# APA102_Shield.net
KiCad netlist of a schematic drawn in EAGLE
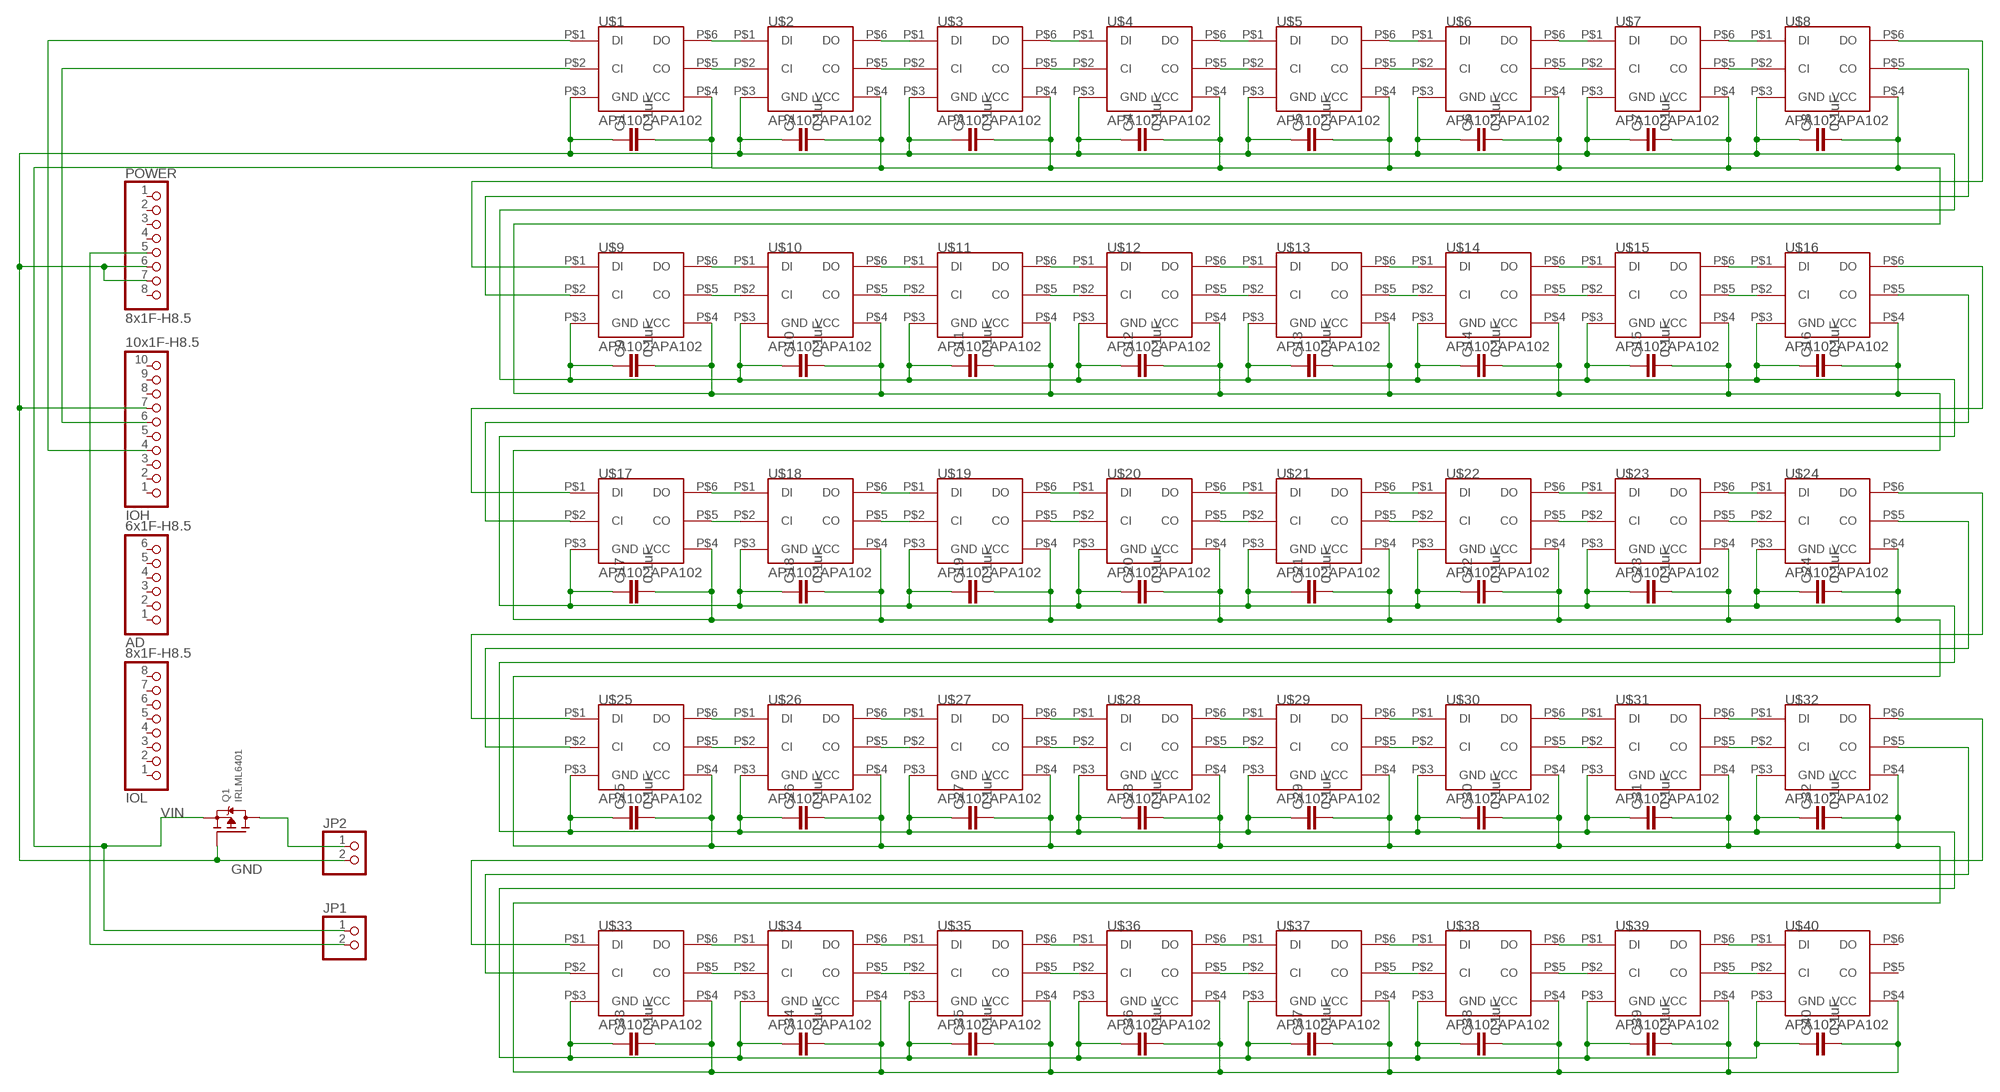
[diagram p0: schematic, sheet 1]

(export (version "E")
  (design (tool "Eeschema 10.0.6"))
  (components
    (comp (ref "AD")
      (value "6x1F-H8.5")
      (footprint "eagle-import:1X06")
      (libsource (lib "eagle-import") (part "PINHD-1X6"))
    )
    (comp (ref "C1")
      (value "0.1uF")
      (footprint "eagle-import:C1206")
      (libsource (lib "eagle-import") (part "C-EUC1206"))
    )
    (comp (ref "C2")
      (value "0.1uF")
      (footprint "eagle-import:C1206")
      (libsource (lib "eagle-import") (part "C-EUC1206"))
    )
    (comp (ref "C3")
      (value "0.1uF")
      (footprint "eagle-import:C1206")
      (libsource (lib "eagle-import") (part "C-EUC1206"))
    )
    (comp (ref "C4")
      (value "0.1uF")
      (footprint "eagle-import:C1206")
      (libsource (lib "eagle-import") (part "C-EUC1206"))
    )
    (comp (ref "C5")
      (value "0.1uF")
      (footprint "eagle-import:C1206")
      (libsource (lib "eagle-import") (part "C-EUC1206"))
    )
    (comp (ref "C6")
      (value "0.1uF")
      (footprint "eagle-import:C1206")
      (libsource (lib "eagle-import") (part "C-EUC1206"))
    )
    (comp (ref "C7")
      (value "0.1uF")
      (footprint "eagle-import:C1206")
      (libsource (lib "eagle-import") (part "C-EUC1206"))
    )
    (comp (ref "C8")
      (value "0.1uF")
      (footprint "eagle-import:C1206")
      (libsource (lib "eagle-import") (part "C-EUC1206"))
    )
    (comp (ref "C9")
      (value "0.1uF")
      (footprint "eagle-import:C1206")
      (libsource (lib "eagle-import") (part "C-EUC1206"))
    )
    (comp (ref "C10")
      (value "0.1uF")
      (footprint "eagle-import:C1206")
      (libsource (lib "eagle-import") (part "C-EUC1206"))
    )
    (comp (ref "C11")
      (value "0.1uF")
      (footprint "eagle-import:C1206")
      (libsource (lib "eagle-import") (part "C-EUC1206"))
    )
    (comp (ref "C12")
      (value "0.1uF")
      (footprint "eagle-import:C1206")
      (libsource (lib "eagle-import") (part "C-EUC1206"))
    )
    (comp (ref "C13")
      (value "0.1uF")
      (footprint "eagle-import:C1206")
      (libsource (lib "eagle-import") (part "C-EUC1206"))
    )
    (comp (ref "C14")
      (value "0.1uF")
      (footprint "eagle-import:C1206")
      (libsource (lib "eagle-import") (part "C-EUC1206"))
    )
    (comp (ref "C15")
      (value "0.1uF")
      (footprint "eagle-import:C1206")
      (libsource (lib "eagle-import") (part "C-EUC1206"))
    )
    (comp (ref "C16")
      (value "0.1uF")
      (footprint "eagle-import:C1206")
      (libsource (lib "eagle-import") (part "C-EUC1206"))
    )
    (comp (ref "C17")
      (value "0.1uF")
      (footprint "eagle-import:C1206")
      (libsource (lib "eagle-import") (part "C-EUC1206"))
    )
    (comp (ref "C18")
      (value "0.1uF")
      (footprint "eagle-import:C1206")
      (libsource (lib "eagle-import") (part "C-EUC1206"))
    )
    (comp (ref "C19")
      (value "0.1uF")
      (footprint "eagle-import:C1206")
      (libsource (lib "eagle-import") (part "C-EUC1206"))
    )
    (comp (ref "C20")
      (value "0.1uF")
      (footprint "eagle-import:C1206")
      (libsource (lib "eagle-import") (part "C-EUC1206"))
    )
    (comp (ref "C21")
      (value "0.1uF")
      (footprint "eagle-import:C1206")
      (libsource (lib "eagle-import") (part "C-EUC1206"))
    )
    (comp (ref "C22")
      (value "0.1uF")
      (footprint "eagle-import:C1206")
      (libsource (lib "eagle-import") (part "C-EUC1206"))
    )
    (comp (ref "C23")
      (value "0.1uF")
      (footprint "eagle-import:C1206")
      (libsource (lib "eagle-import") (part "C-EUC1206"))
    )
    (comp (ref "C24")
      (value "0.1uF")
      (footprint "eagle-import:C1206")
      (libsource (lib "eagle-import") (part "C-EUC1206"))
    )
    (comp (ref "C25")
      (value "0.1uF")
      (footprint "eagle-import:C1206")
      (libsource (lib "eagle-import") (part "C-EUC1206"))
    )
    (comp (ref "C26")
      (value "0.1uF")
      (footprint "eagle-import:C1206")
      (libsource (lib "eagle-import") (part "C-EUC1206"))
    )
    (comp (ref "C27")
      (value "0.1uF")
      (footprint "eagle-import:C1206")
      (libsource (lib "eagle-import") (part "C-EUC1206"))
    )
    (comp (ref "C28")
      (value "0.1uF")
      (footprint "eagle-import:C1206")
      (libsource (lib "eagle-import") (part "C-EUC1206"))
    )
    (comp (ref "C29")
      (value "0.1uF")
      (footprint "eagle-import:C1206")
      (libsource (lib "eagle-import") (part "C-EUC1206"))
    )
    (comp (ref "C30")
      (value "0.1uF")
      (footprint "eagle-import:C1206")
      (libsource (lib "eagle-import") (part "C-EUC1206"))
    )
    (comp (ref "C31")
      (value "0.1uF")
      (footprint "eagle-import:C1206")
      (libsource (lib "eagle-import") (part "C-EUC1206"))
    )
    (comp (ref "C32")
      (value "0.1uF")
      (footprint "eagle-import:C1206")
      (libsource (lib "eagle-import") (part "C-EUC1206"))
    )
    (comp (ref "C33")
      (value "0.1uF")
      (footprint "eagle-import:C1206")
      (libsource (lib "eagle-import") (part "C-EUC1206"))
    )
    (comp (ref "C34")
      (value "0.1uF")
      (footprint "eagle-import:C1206")
      (libsource (lib "eagle-import") (part "C-EUC1206"))
    )
    (comp (ref "C35")
      (value "0.1uF")
      (footprint "eagle-import:C1206")
      (libsource (lib "eagle-import") (part "C-EUC1206"))
    )
    (comp (ref "C36")
      (value "0.1uF")
      (footprint "eagle-import:C1206")
      (libsource (lib "eagle-import") (part "C-EUC1206"))
    )
    (comp (ref "C37")
      (value "0.1uF")
      (footprint "eagle-import:C1206")
      (libsource (lib "eagle-import") (part "C-EUC1206"))
    )
    (comp (ref "C38")
      (value "0.1uF")
      (footprint "eagle-import:C1206")
      (libsource (lib "eagle-import") (part "C-EUC1206"))
    )
    (comp (ref "C39")
      (value "0.1uF")
      (footprint "eagle-import:C1206")
      (libsource (lib "eagle-import") (part "C-EUC1206"))
    )
    (comp (ref "C40")
      (value "0.1uF")
      (footprint "eagle-import:C1206")
      (libsource (lib "eagle-import") (part "C-EUC1206"))
    )
    (comp (ref "IOH")
      (value "10x1F-H8.5")
      (footprint "eagle-import:1X10")
      (libsource (lib "eagle-import") (part "PINHD-1X10_ARD"))
    )
    (comp (ref "IOL")
      (value "8x1F-H8.5")
      (footprint "eagle-import:1X08")
      (libsource (lib "eagle-import") (part "PINHD-1X8"))
    )
    (comp (ref "JP1")
      (value "PINHD-1X2")
      (footprint "eagle-import:1X02")
      (libsource (lib "eagle-import") (part "PINHD-1X2"))
    )
    (comp (ref "JP2")
      (value "PINHD-1X2")
      (footprint "eagle-import:1X02")
      (libsource (lib "eagle-import") (part "PINHD-1X2"))
    )
    (comp (ref "POWER")
      (value "8x1F-H8.5")
      (footprint "eagle-import:1X08")
      (libsource (lib "eagle-import") (part "PINHD-1X8"))
    )
    (comp (ref "Q1")
      (value "IRLML6401")
      (footprint "eagle-import:SOT23-WIDE")
      (libsource (lib "eagle-import") (part "MOSFET-PWIDE"))
    )
    (comp (ref "U$1")
      (value "APA102APA102")
      (footprint "eagle-import:5050")
      (libsource (lib "eagle-import") (part "APA102APA102"))
    )
    (comp (ref "U$2")
      (value "APA102APA102")
      (footprint "eagle-import:5050")
      (libsource (lib "eagle-import") (part "APA102APA102"))
    )
    (comp (ref "U$3")
      (value "APA102APA102")
      (footprint "eagle-import:5050")
      (libsource (lib "eagle-import") (part "APA102APA102"))
    )
    (comp (ref "U$4")
      (value "APA102APA102")
      (footprint "eagle-import:5050")
      (libsource (lib "eagle-import") (part "APA102APA102"))
    )
    (comp (ref "U$5")
      (value "APA102APA102")
      (footprint "eagle-import:5050")
      (libsource (lib "eagle-import") (part "APA102APA102"))
    )
    (comp (ref "U$6")
      (value "APA102APA102")
      (footprint "eagle-import:5050")
      (libsource (lib "eagle-import") (part "APA102APA102"))
    )
    (comp (ref "U$7")
      (value "APA102APA102")
      (footprint "eagle-import:5050")
      (libsource (lib "eagle-import") (part "APA102APA102"))
    )
    (comp (ref "U$8")
      (value "APA102APA102")
      (footprint "eagle-import:5050")
      (libsource (lib "eagle-import") (part "APA102APA102"))
    )
    (comp (ref "U$9")
      (value "APA102APA102")
      (footprint "eagle-import:5050")
      (libsource (lib "eagle-import") (part "APA102APA102"))
    )
    (comp (ref "U$10")
      (value "APA102APA102")
      (footprint "eagle-import:5050")
      (libsource (lib "eagle-import") (part "APA102APA102"))
    )
    (comp (ref "U$11")
      (value "APA102APA102")
      (footprint "eagle-import:5050")
      (libsource (lib "eagle-import") (part "APA102APA102"))
    )
    (comp (ref "U$12")
      (value "APA102APA102")
      (footprint "eagle-import:5050")
      (libsource (lib "eagle-import") (part "APA102APA102"))
    )
    (comp (ref "U$13")
      (value "APA102APA102")
      (footprint "eagle-import:5050")
      (libsource (lib "eagle-import") (part "APA102APA102"))
    )
    (comp (ref "U$14")
      (value "APA102APA102")
      (footprint "eagle-import:5050")
      (libsource (lib "eagle-import") (part "APA102APA102"))
    )
    (comp (ref "U$15")
      (value "APA102APA102")
      (footprint "eagle-import:5050")
      (libsource (lib "eagle-import") (part "APA102APA102"))
    )
    (comp (ref "U$16")
      (value "APA102APA102")
      (footprint "eagle-import:5050")
      (libsource (lib "eagle-import") (part "APA102APA102"))
    )
    (comp (ref "U$17")
      (value "APA102APA102")
      (footprint "eagle-import:5050")
      (libsource (lib "eagle-import") (part "APA102APA102"))
    )
    (comp (ref "U$18")
      (value "APA102APA102")
      (footprint "eagle-import:5050")
      (libsource (lib "eagle-import") (part "APA102APA102"))
    )
    (comp (ref "U$19")
      (value "APA102APA102")
      (footprint "eagle-import:5050")
      (libsource (lib "eagle-import") (part "APA102APA102"))
    )
    (comp (ref "U$20")
      (value "APA102APA102")
      (footprint "eagle-import:5050")
      (libsource (lib "eagle-import") (part "APA102APA102"))
    )
    (comp (ref "U$21")
      (value "APA102APA102")
      (footprint "eagle-import:5050")
      (libsource (lib "eagle-import") (part "APA102APA102"))
    )
    (comp (ref "U$22")
      (value "APA102APA102")
      (footprint "eagle-import:5050")
      (libsource (lib "eagle-import") (part "APA102APA102"))
    )
    (comp (ref "U$23")
      (value "APA102APA102")
      (footprint "eagle-import:5050")
      (libsource (lib "eagle-import") (part "APA102APA102"))
    )
    (comp (ref "U$24")
      (value "APA102APA102")
      (footprint "eagle-import:5050")
      (libsource (lib "eagle-import") (part "APA102APA102"))
    )
    (comp (ref "U$25")
      (value "APA102APA102")
      (footprint "eagle-import:5050")
      (libsource (lib "eagle-import") (part "APA102APA102"))
    )
    (comp (ref "U$26")
      (value "APA102APA102")
      (footprint "eagle-import:5050")
      (libsource (lib "eagle-import") (part "APA102APA102"))
    )
    (comp (ref "U$27")
      (value "APA102APA102")
      (footprint "eagle-import:5050")
      (libsource (lib "eagle-import") (part "APA102APA102"))
    )
    (comp (ref "U$28")
      (value "APA102APA102")
      (footprint "eagle-import:5050")
      (libsource (lib "eagle-import") (part "APA102APA102"))
    )
    (comp (ref "U$29")
      (value "APA102APA102")
      (footprint "eagle-import:5050")
      (libsource (lib "eagle-import") (part "APA102APA102"))
    )
    (comp (ref "U$30")
      (value "APA102APA102")
      (footprint "eagle-import:5050")
      (libsource (lib "eagle-import") (part "APA102APA102"))
    )
    (comp (ref "U$31")
      (value "APA102APA102")
      (footprint "eagle-import:5050")
      (libsource (lib "eagle-import") (part "APA102APA102"))
    )
    (comp (ref "U$32")
      (value "APA102APA102")
      (footprint "eagle-import:5050")
      (libsource (lib "eagle-import") (part "APA102APA102"))
    )
    (comp (ref "U$33")
      (value "APA102APA102")
      (footprint "eagle-import:5050")
      (libsource (lib "eagle-import") (part "APA102APA102"))
    )
    (comp (ref "U$34")
      (value "APA102APA102")
      (footprint "eagle-import:5050")
      (libsource (lib "eagle-import") (part "APA102APA102"))
    )
    (comp (ref "U$35")
      (value "APA102APA102")
      (footprint "eagle-import:5050")
      (libsource (lib "eagle-import") (part "APA102APA102"))
    )
    (comp (ref "U$36")
      (value "APA102APA102")
      (footprint "eagle-import:5050")
      (libsource (lib "eagle-import") (part "APA102APA102"))
    )
    (comp (ref "U$37")
      (value "APA102APA102")
      (footprint "eagle-import:5050")
      (libsource (lib "eagle-import") (part "APA102APA102"))
    )
    (comp (ref "U$38")
      (value "APA102APA102")
      (footprint "eagle-import:5050")
      (libsource (lib "eagle-import") (part "APA102APA102"))
    )
    (comp (ref "U$39")
      (value "APA102APA102")
      (footprint "eagle-import:5050")
      (libsource (lib "eagle-import") (part "APA102APA102"))
    )
    (comp (ref "U$40")
      (value "APA102APA102")
      (footprint "eagle-import:5050")
      (libsource (lib "eagle-import") (part "APA102APA102"))
    )
  )
  (nets
    (net (code "1") (name "/GND") (class "Default")
      (node (ref "C1") (pin "1") (pinfunction "1_1") (pintype "passive"))
      (node (ref "C10") (pin "1") (pinfunction "1_1") (pintype "passive"))
      (node (ref "C11") (pin "1") (pinfunction "1_1") (pintype "passive"))
      (node (ref "C12") (pin "1") (pinfunction "1_1") (pintype "passive"))
      (node (ref "C13") (pin "1") (pinfunction "1_1") (pintype "passive"))
      (node (ref "C14") (pin "1") (pinfunction "1_1") (pintype "passive"))
      (node (ref "C15") (pin "1") (pinfunction "1_1") (pintype "passive"))
      (node (ref "C16") (pin "1") (pinfunction "1_1") (pintype "passive"))
      (node (ref "C17") (pin "1") (pinfunction "1_1") (pintype "passive"))
      (node (ref "C18") (pin "1") (pinfunction "1_1") (pintype "passive"))
      (node (ref "C19") (pin "1") (pinfunction "1_1") (pintype "passive"))
      (node (ref "C2") (pin "1") (pinfunction "1_1") (pintype "passive"))
      (node (ref "C20") (pin "1") (pinfunction "1_1") (pintype "passive"))
      (node (ref "C21") (pin "1") (pinfunction "1_1") (pintype "passive"))
      (node (ref "C22") (pin "1") (pinfunction "1_1") (pintype "passive"))
      (node (ref "C23") (pin "1") (pinfunction "1_1") (pintype "passive"))
      (node (ref "C24") (pin "1") (pinfunction "1_1") (pintype "passive"))
      (node (ref "C25") (pin "1") (pinfunction "1_1") (pintype "passive"))
      (node (ref "C26") (pin "1") (pinfunction "1_1") (pintype "passive"))
      (node (ref "C27") (pin "1") (pinfunction "1_1") (pintype "passive"))
      (node (ref "C28") (pin "1") (pinfunction "1_1") (pintype "passive"))
      (node (ref "C29") (pin "1") (pinfunction "1_1") (pintype "passive"))
      (node (ref "C3") (pin "1") (pinfunction "1_1") (pintype "passive"))
      (node (ref "C30") (pin "1") (pinfunction "1_1") (pintype "passive"))
      (node (ref "C31") (pin "1") (pinfunction "1_1") (pintype "passive"))
      (node (ref "C32") (pin "1") (pinfunction "1_1") (pintype "passive"))
      (node (ref "C33") (pin "1") (pinfunction "1_1") (pintype "passive"))
      (node (ref "C34") (pin "1") (pinfunction "1_1") (pintype "passive"))
      (node (ref "C35") (pin "1") (pinfunction "1_1") (pintype "passive"))
      (node (ref "C36") (pin "1") (pinfunction "1_1") (pintype "passive"))
      (node (ref "C37") (pin "1") (pinfunction "1_1") (pintype "passive"))
      (node (ref "C38") (pin "1") (pinfunction "1_1") (pintype "passive"))
      (node (ref "C39") (pin "1") (pinfunction "1_1") (pintype "passive"))
      (node (ref "C4") (pin "1") (pinfunction "1_1") (pintype "passive"))
      (node (ref "C40") (pin "1") (pinfunction "1_1") (pintype "passive"))
      (node (ref "C5") (pin "1") (pinfunction "1_1") (pintype "passive"))
      (node (ref "C6") (pin "1") (pinfunction "1_1") (pintype "passive"))
      (node (ref "C7") (pin "1") (pinfunction "1_1") (pintype "passive"))
      (node (ref "C8") (pin "1") (pinfunction "1_1") (pintype "passive"))
      (node (ref "C9") (pin "1") (pinfunction "1_1") (pintype "passive"))
      (node (ref "IOH") (pin "7") (pinfunction "7_7") (pintype "passive"))
      (node (ref "JP2") (pin "2") (pinfunction "2_2") (pintype "passive"))
      (node (ref "POWER") (pin "6") (pinfunction "6_6") (pintype "passive"))
      (node (ref "POWER") (pin "7") (pinfunction "7_7") (pintype "passive"))
      (node (ref "Q1") (pin "1") (pinfunction "G_1") (pintype "passive"))
      (node (ref "U$1") (pin "P$3") (pinfunction "GND_P$3") (pintype "bidirectional"))
      (node (ref "U$10") (pin "P$3") (pinfunction "GND_P$3") (pintype "bidirectional"))
      (node (ref "U$11") (pin "P$3") (pinfunction "GND_P$3") (pintype "bidirectional"))
      (node (ref "U$12") (pin "P$3") (pinfunction "GND_P$3") (pintype "bidirectional"))
      (node (ref "U$13") (pin "P$3") (pinfunction "GND_P$3") (pintype "bidirectional"))
      (node (ref "U$14") (pin "P$3") (pinfunction "GND_P$3") (pintype "bidirectional"))
      (node (ref "U$15") (pin "P$3") (pinfunction "GND_P$3") (pintype "bidirectional"))
      (node (ref "U$16") (pin "P$3") (pinfunction "GND_P$3") (pintype "bidirectional"))
      (node (ref "U$17") (pin "P$3") (pinfunction "GND_P$3") (pintype "bidirectional"))
      (node (ref "U$18") (pin "P$3") (pinfunction "GND_P$3") (pintype "bidirectional"))
      (node (ref "U$19") (pin "P$3") (pinfunction "GND_P$3") (pintype "bidirectional"))
      (node (ref "U$2") (pin "P$3") (pinfunction "GND_P$3") (pintype "bidirectional"))
      (node (ref "U$20") (pin "P$3") (pinfunction "GND_P$3") (pintype "bidirectional"))
      (node (ref "U$21") (pin "P$3") (pinfunction "GND_P$3") (pintype "bidirectional"))
      (node (ref "U$22") (pin "P$3") (pinfunction "GND_P$3") (pintype "bidirectional"))
      (node (ref "U$23") (pin "P$3") (pinfunction "GND_P$3") (pintype "bidirectional"))
      (node (ref "U$24") (pin "P$3") (pinfunction "GND_P$3") (pintype "bidirectional"))
      (node (ref "U$25") (pin "P$3") (pinfunction "GND_P$3") (pintype "bidirectional"))
      (node (ref "U$26") (pin "P$3") (pinfunction "GND_P$3") (pintype "bidirectional"))
      (node (ref "U$27") (pin "P$3") (pinfunction "GND_P$3") (pintype "bidirectional"))
      (node (ref "U$28") (pin "P$3") (pinfunction "GND_P$3") (pintype "bidirectional"))
      (node (ref "U$29") (pin "P$3") (pinfunction "GND_P$3") (pintype "bidirectional"))
      (node (ref "U$3") (pin "P$3") (pinfunction "GND_P$3") (pintype "bidirectional"))
      (node (ref "U$30") (pin "P$3") (pinfunction "GND_P$3") (pintype "bidirectional"))
      (node (ref "U$31") (pin "P$3") (pinfunction "GND_P$3") (pintype "bidirectional"))
      (node (ref "U$32") (pin "P$3") (pinfunction "GND_P$3") (pintype "bidirectional"))
      (node (ref "U$33") (pin "P$3") (pinfunction "GND_P$3") (pintype "bidirectional"))
      (node (ref "U$34") (pin "P$3") (pinfunction "GND_P$3") (pintype "bidirectional"))
      (node (ref "U$35") (pin "P$3") (pinfunction "GND_P$3") (pintype "bidirectional"))
      (node (ref "U$36") (pin "P$3") (pinfunction "GND_P$3") (pintype "bidirectional"))
      (node (ref "U$37") (pin "P$3") (pinfunction "GND_P$3") (pintype "bidirectional"))
      (node (ref "U$38") (pin "P$3") (pinfunction "GND_P$3") (pintype "bidirectional"))
      (node (ref "U$39") (pin "P$3") (pinfunction "GND_P$3") (pintype "bidirectional"))
      (node (ref "U$4") (pin "P$3") (pinfunction "GND_P$3") (pintype "bidirectional"))
      (node (ref "U$40") (pin "P$3") (pinfunction "GND_P$3") (pintype "bidirectional"))
      (node (ref "U$5") (pin "P$3") (pinfunction "GND_P$3") (pintype "bidirectional"))
      (node (ref "U$6") (pin "P$3") (pinfunction "GND_P$3") (pintype "bidirectional"))
      (node (ref "U$7") (pin "P$3") (pinfunction "GND_P$3") (pintype "bidirectional"))
      (node (ref "U$8") (pin "P$3") (pinfunction "GND_P$3") (pintype "bidirectional"))
      (node (ref "U$9") (pin "P$3") (pinfunction "GND_P$3") (pintype "bidirectional"))
    )
    (net (code "2") (name "/VIN") (class "Default")
      (node (ref "C1") (pin "2") (pinfunction "2_2") (pintype "passive"))
      (node (ref "C10") (pin "2") (pinfunction "2_2") (pintype "passive"))
      (node (ref "C11") (pin "2") (pinfunction "2_2") (pintype "passive"))
      (node (ref "C12") (pin "2") (pinfunction "2_2") (pintype "passive"))
      (node (ref "C13") (pin "2") (pinfunction "2_2") (pintype "passive"))
      (node (ref "C14") (pin "2") (pinfunction "2_2") (pintype "passive"))
      (node (ref "C15") (pin "2") (pinfunction "2_2") (pintype "passive"))
      (node (ref "C16") (pin "2") (pinfunction "2_2") (pintype "passive"))
      (node (ref "C17") (pin "2") (pinfunction "2_2") (pintype "passive"))
      (node (ref "C18") (pin "2") (pinfunction "2_2") (pintype "passive"))
      (node (ref "C19") (pin "2") (pinfunction "2_2") (pintype "passive"))
      (node (ref "C2") (pin "2") (pinfunction "2_2") (pintype "passive"))
      (node (ref "C20") (pin "2") (pinfunction "2_2") (pintype "passive"))
      (node (ref "C21") (pin "2") (pinfunction "2_2") (pintype "passive"))
      (node (ref "C22") (pin "2") (pinfunction "2_2") (pintype "passive"))
      (node (ref "C23") (pin "2") (pinfunction "2_2") (pintype "passive"))
      (node (ref "C24") (pin "2") (pinfunction "2_2") (pintype "passive"))
      (node (ref "C25") (pin "2") (pinfunction "2_2") (pintype "passive"))
      (node (ref "C26") (pin "2") (pinfunction "2_2") (pintype "passive"))
      (node (ref "C27") (pin "2") (pinfunction "2_2") (pintype "passive"))
      (node (ref "C28") (pin "2") (pinfunction "2_2") (pintype "passive"))
      (node (ref "C29") (pin "2") (pinfunction "2_2") (pintype "passive"))
      (node (ref "C3") (pin "2") (pinfunction "2_2") (pintype "passive"))
      (node (ref "C30") (pin "2") (pinfunction "2_2") (pintype "passive"))
      (node (ref "C31") (pin "2") (pinfunction "2_2") (pintype "passive"))
      (node (ref "C32") (pin "2") (pinfunction "2_2") (pintype "passive"))
      (node (ref "C33") (pin "2") (pinfunction "2_2") (pintype "passive"))
      (node (ref "C34") (pin "2") (pinfunction "2_2") (pintype "passive"))
      (node (ref "C35") (pin "2") (pinfunction "2_2") (pintype "passive"))
      (node (ref "C36") (pin "2") (pinfunction "2_2") (pintype "passive"))
      (node (ref "C37") (pin "2") (pinfunction "2_2") (pintype "passive"))
      (node (ref "C38") (pin "2") (pinfunction "2_2") (pintype "passive"))
      (node (ref "C39") (pin "2") (pinfunction "2_2") (pintype "passive"))
      (node (ref "C4") (pin "2") (pinfunction "2_2") (pintype "passive"))
      (node (ref "C40") (pin "2") (pinfunction "2_2") (pintype "passive"))
      (node (ref "C5") (pin "2") (pinfunction "2_2") (pintype "passive"))
      (node (ref "C6") (pin "2") (pinfunction "2_2") (pintype "passive"))
      (node (ref "C7") (pin "2") (pinfunction "2_2") (pintype "passive"))
      (node (ref "C8") (pin "2") (pinfunction "2_2") (pintype "passive"))
      (node (ref "C9") (pin "2") (pinfunction "2_2") (pintype "passive"))
      (node (ref "JP1") (pin "1") (pinfunction "1_1") (pintype "passive"))
      (node (ref "Q1") (pin "2") (pinfunction "S_2") (pintype "passive"))
      (node (ref "U$1") (pin "P$4") (pinfunction "VCC_P$4") (pintype "bidirectional"))
      (node (ref "U$10") (pin "P$4") (pinfunction "VCC_P$4") (pintype "bidirectional"))
      (node (ref "U$11") (pin "P$4") (pinfunction "VCC_P$4") (pintype "bidirectional"))
      (node (ref "U$12") (pin "P$4") (pinfunction "VCC_P$4") (pintype "bidirectional"))
      (node (ref "U$13") (pin "P$4") (pinfunction "VCC_P$4") (pintype "bidirectional"))
      (node (ref "U$14") (pin "P$4") (pinfunction "VCC_P$4") (pintype "bidirectional"))
      (node (ref "U$15") (pin "P$4") (pinfunction "VCC_P$4") (pintype "bidirectional"))
      (node (ref "U$16") (pin "P$4") (pinfunction "VCC_P$4") (pintype "bidirectional"))
      (node (ref "U$17") (pin "P$4") (pinfunction "VCC_P$4") (pintype "bidirectional"))
      (node (ref "U$18") (pin "P$4") (pinfunction "VCC_P$4") (pintype "bidirectional"))
      (node (ref "U$19") (pin "P$4") (pinfunction "VCC_P$4") (pintype "bidirectional"))
      (node (ref "U$2") (pin "P$4") (pinfunction "VCC_P$4") (pintype "bidirectional"))
      (node (ref "U$20") (pin "P$4") (pinfunction "VCC_P$4") (pintype "bidirectional"))
      (node (ref "U$21") (pin "P$4") (pinfunction "VCC_P$4") (pintype "bidirectional"))
      (node (ref "U$22") (pin "P$4") (pinfunction "VCC_P$4") (pintype "bidirectional"))
      (node (ref "U$23") (pin "P$4") (pinfunction "VCC_P$4") (pintype "bidirectional"))
      (node (ref "U$24") (pin "P$4") (pinfunction "VCC_P$4") (pintype "bidirectional"))
      (node (ref "U$25") (pin "P$4") (pinfunction "VCC_P$4") (pintype "bidirectional"))
      (node (ref "U$26") (pin "P$4") (pinfunction "VCC_P$4") (pintype "bidirectional"))
      (node (ref "U$27") (pin "P$4") (pinfunction "VCC_P$4") (pintype "bidirectional"))
      (node (ref "U$28") (pin "P$4") (pinfunction "VCC_P$4") (pintype "bidirectional"))
      (node (ref "U$29") (pin "P$4") (pinfunction "VCC_P$4") (pintype "bidirectional"))
      (node (ref "U$3") (pin "P$4") (pinfunction "VCC_P$4") (pintype "bidirectional"))
      (node (ref "U$30") (pin "P$4") (pinfunction "VCC_P$4") (pintype "bidirectional"))
      (node (ref "U$31") (pin "P$4") (pinfunction "VCC_P$4") (pintype "bidirectional"))
      (node (ref "U$32") (pin "P$4") (pinfunction "VCC_P$4") (pintype "bidirectional"))
      (node (ref "U$33") (pin "P$4") (pinfunction "VCC_P$4") (pintype "bidirectional"))
      (node (ref "U$34") (pin "P$4") (pinfunction "VCC_P$4") (pintype "bidirectional"))
      (node (ref "U$35") (pin "P$4") (pinfunction "VCC_P$4") (pintype "bidirectional"))
      (node (ref "U$36") (pin "P$4") (pinfunction "VCC_P$4") (pintype "bidirectional"))
      (node (ref "U$37") (pin "P$4") (pinfunction "VCC_P$4") (pintype "bidirectional"))
      (node (ref "U$38") (pin "P$4") (pinfunction "VCC_P$4") (pintype "bidirectional"))
      (node (ref "U$39") (pin "P$4") (pinfunction "VCC_P$4") (pintype "bidirectional"))
      (node (ref "U$4") (pin "P$4") (pinfunction "VCC_P$4") (pintype "bidirectional"))
      (node (ref "U$40") (pin "P$4") (pinfunction "VCC_P$4") (pintype "bidirectional"))
      (node (ref "U$5") (pin "P$4") (pinfunction "VCC_P$4") (pintype "bidirectional"))
      (node (ref "U$6") (pin "P$4") (pinfunction "VCC_P$4") (pintype "bidirectional"))
      (node (ref "U$7") (pin "P$4") (pinfunction "VCC_P$4") (pintype "bidirectional"))
      (node (ref "U$8") (pin "P$4") (pinfunction "VCC_P$4") (pintype "bidirectional"))
      (node (ref "U$9") (pin "P$4") (pinfunction "VCC_P$4") (pintype "bidirectional"))
    )
    (net (code "3") (name "Net-(JP1-Pad2)") (class "Default")
      (node (ref "JP1") (pin "2") (pinfunction "2_2") (pintype "passive"))
      (node (ref "POWER") (pin "5") (pinfunction "5_5") (pintype "passive"))
    )
    (net (code "4") (name "Net-(Q1-D)") (class "Default")
      (node (ref "JP2") (pin "1") (pinfunction "1_1") (pintype "passive"))
      (node (ref "Q1") (pin "3") (pinfunction "D_3") (pintype "passive"))
    )
    (net (code "5") (name "Net-(U$1-CI)") (class "Default")
      (node (ref "IOH") (pin "6") (pinfunction "6_6") (pintype "passive"))
      (node (ref "U$1") (pin "P$2") (pinfunction "CI_P$2") (pintype "bidirectional"))
    )
    (net (code "6") (name "Net-(U$1-CO)") (class "Default")
      (node (ref "U$1") (pin "P$5") (pinfunction "CO_P$5") (pintype "bidirectional"))
      (node (ref "U$2") (pin "P$2") (pinfunction "CI_P$2") (pintype "bidirectional"))
    )
    (net (code "7") (name "Net-(U$1-DI)") (class "Default")
      (node (ref "IOH") (pin "4") (pinfunction "4_4") (pintype "passive"))
      (node (ref "U$1") (pin "P$1") (pinfunction "DI_P$1") (pintype "bidirectional"))
    )
    (net (code "8") (name "Net-(U$1-DO)") (class "Default")
      (node (ref "U$1") (pin "P$6") (pinfunction "DO_P$6") (pintype "bidirectional"))
      (node (ref "U$2") (pin "P$1") (pinfunction "DI_P$1") (pintype "bidirectional"))
    )
    (net (code "9") (name "Net-(U$2-CO)") (class "Default")
      (node (ref "U$2") (pin "P$5") (pinfunction "CO_P$5") (pintype "bidirectional"))
      (node (ref "U$3") (pin "P$2") (pinfunction "CI_P$2") (pintype "bidirectional"))
    )
    (net (code "10") (name "Net-(U$2-DO)") (class "Default")
      (node (ref "U$2") (pin "P$6") (pinfunction "DO_P$6") (pintype "bidirectional"))
      (node (ref "U$3") (pin "P$1") (pinfunction "DI_P$1") (pintype "bidirectional"))
    )
    (net (code "11") (name "Net-(U$3-CO)") (class "Default")
      (node (ref "U$3") (pin "P$5") (pinfunction "CO_P$5") (pintype "bidirectional"))
      (node (ref "U$4") (pin "P$2") (pinfunction "CI_P$2") (pintype "bidirectional"))
    )
    (net (code "12") (name "Net-(U$3-DO)") (class "Default")
      (node (ref "U$3") (pin "P$6") (pinfunction "DO_P$6") (pintype "bidirectional"))
      (node (ref "U$4") (pin "P$1") (pinfunction "DI_P$1") (pintype "bidirectional"))
    )
    (net (code "13") (name "Net-(U$4-CO)") (class "Default")
      (node (ref "U$4") (pin "P$5") (pinfunction "CO_P$5") (pintype "bidirectional"))
      (node (ref "U$5") (pin "P$2") (pinfunction "CI_P$2") (pintype "bidirectional"))
    )
    (net (code "14") (name "Net-(U$4-DO)") (class "Default")
      (node (ref "U$4") (pin "P$6") (pinfunction "DO_P$6") (pintype "bidirectional"))
      (node (ref "U$5") (pin "P$1") (pinfunction "DI_P$1") (pintype "bidirectional"))
    )
    (net (code "15") (name "Net-(U$5-CO)") (class "Default")
      (node (ref "U$5") (pin "P$5") (pinfunction "CO_P$5") (pintype "bidirectional"))
      (node (ref "U$6") (pin "P$2") (pinfunction "CI_P$2") (pintype "bidirectional"))
    )
    (net (code "16") (name "Net-(U$5-DO)") (class "Default")
      (node (ref "U$5") (pin "P$6") (pinfunction "DO_P$6") (pintype "bidirectional"))
      (node (ref "U$6") (pin "P$1") (pinfunction "DI_P$1") (pintype "bidirectional"))
    )
    (net (code "17") (name "Net-(U$6-CO)") (class "Default")
      (node (ref "U$6") (pin "P$5") (pinfunction "CO_P$5") (pintype "bidirectional"))
      (node (ref "U$7") (pin "P$2") (pinfunction "CI_P$2") (pintype "bidirectional"))
    )
    (net (code "18") (name "Net-(U$6-DO)") (class "Default")
      (node (ref "U$6") (pin "P$6") (pinfunction "DO_P$6") (pintype "bidirectional"))
      (node (ref "U$7") (pin "P$1") (pinfunction "DI_P$1") (pintype "bidirectional"))
    )
    (net (code "19") (name "Net-(U$7-CO)") (class "Default")
      (node (ref "U$7") (pin "P$5") (pinfunction "CO_P$5") (pintype "bidirectional"))
      (node (ref "U$8") (pin "P$2") (pinfunction "CI_P$2") (pintype "bidirectional"))
    )
    (net (code "20") (name "Net-(U$7-DO)") (class "Default")
      (node (ref "U$7") (pin "P$6") (pinfunction "DO_P$6") (pintype "bidirectional"))
      (node (ref "U$8") (pin "P$1") (pinfunction "DI_P$1") (pintype "bidirectional"))
    )
    (net (code "21") (name "Net-(U$8-CO)") (class "Default")
      (node (ref "U$8") (pin "P$5") (pinfunction "CO_P$5") (pintype "bidirectional"))
      (node (ref "U$9") (pin "P$2") (pinfunction "CI_P$2") (pintype "bidirectional"))
    )
    (net (code "22") (name "Net-(U$8-DO)") (class "Default")
      (node (ref "U$8") (pin "P$6") (pinfunction "DO_P$6") (pintype "bidirectional"))
      (node (ref "U$9") (pin "P$1") (pinfunction "DI_P$1") (pintype "bidirectional"))
    )
    (net (code "23") (name "Net-(U$10-CI)") (class "Default")
      (node (ref "U$10") (pin "P$2") (pinfunction "CI_P$2") (pintype "bidirectional"))
      (node (ref "U$9") (pin "P$5") (pinfunction "CO_P$5") (pintype "bidirectional"))
    )
    (net (code "24") (name "Net-(U$10-CO)") (class "Default")
      (node (ref "U$10") (pin "P$5") (pinfunction "CO_P$5") (pintype "bidirectional"))
      (node (ref "U$11") (pin "P$2") (pinfunction "CI_P$2") (pintype "bidirectional"))
    )
    (net (code "25") (name "Net-(U$10-DI)") (class "Default")
      (node (ref "U$10") (pin "P$1") (pinfunction "DI_P$1") (pintype "bidirectional"))
      (node (ref "U$9") (pin "P$6") (pinfunction "DO_P$6") (pintype "bidirectional"))
    )
    (net (code "26") (name "Net-(U$10-DO)") (class "Default")
      (node (ref "U$10") (pin "P$6") (pinfunction "DO_P$6") (pintype "bidirectional"))
      (node (ref "U$11") (pin "P$1") (pinfunction "DI_P$1") (pintype "bidirectional"))
    )
    (net (code "27") (name "Net-(U$11-CO)") (class "Default")
      (node (ref "U$11") (pin "P$5") (pinfunction "CO_P$5") (pintype "bidirectional"))
      (node (ref "U$12") (pin "P$2") (pinfunction "CI_P$2") (pintype "bidirectional"))
    )
    (net (code "28") (name "Net-(U$11-DO)") (class "Default")
      (node (ref "U$11") (pin "P$6") (pinfunction "DO_P$6") (pintype "bidirectional"))
      (node (ref "U$12") (pin "P$1") (pinfunction "DI_P$1") (pintype "bidirectional"))
    )
    (net (code "29") (name "Net-(U$12-CO)") (class "Default")
      (node (ref "U$12") (pin "P$5") (pinfunction "CO_P$5") (pintype "bidirectional"))
      (node (ref "U$13") (pin "P$2") (pinfunction "CI_P$2") (pintype "bidirectional"))
    )
    (net (code "30") (name "Net-(U$12-DO)") (class "Default")
      (node (ref "U$12") (pin "P$6") (pinfunction "DO_P$6") (pintype "bidirectional"))
      (node (ref "U$13") (pin "P$1") (pinfunction "DI_P$1") (pintype "bidirectional"))
    )
    (net (code "31") (name "Net-(U$13-CO)") (class "Default")
      (node (ref "U$13") (pin "P$5") (pinfunction "CO_P$5") (pintype "bidirectional"))
      (node (ref "U$14") (pin "P$2") (pinfunction "CI_P$2") (pintype "bidirectional"))
    )
    (net (code "32") (name "Net-(U$13-DO)") (class "Default")
      (node (ref "U$13") (pin "P$6") (pinfunction "DO_P$6") (pintype "bidirectional"))
      (node (ref "U$14") (pin "P$1") (pinfunction "DI_P$1") (pintype "bidirectional"))
    )
    (net (code "33") (name "Net-(U$14-CO)") (class "Default")
      (node (ref "U$14") (pin "P$5") (pinfunction "CO_P$5") (pintype "bidirectional"))
      (node (ref "U$15") (pin "P$2") (pinfunction "CI_P$2") (pintype "bidirectional"))
    )
    (net (code "34") (name "Net-(U$14-DO)") (class "Default")
      (node (ref "U$14") (pin "P$6") (pinfunction "DO_P$6") (pintype "bidirectional"))
      (node (ref "U$15") (pin "P$1") (pinfunction "DI_P$1") (pintype "bidirectional"))
    )
    (net (code "35") (name "Net-(U$15-CO)") (class "Default")
      (node (ref "U$15") (pin "P$5") (pinfunction "CO_P$5") (pintype "bidirectional"))
      (node (ref "U$16") (pin "P$2") (pinfunction "CI_P$2") (pintype "bidirectional"))
    )
    (net (code "36") (name "Net-(U$15-DO)") (class "Default")
      (node (ref "U$15") (pin "P$6") (pinfunction "DO_P$6") (pintype "bidirectional"))
      (node (ref "U$16") (pin "P$1") (pinfunction "DI_P$1") (pintype "bidirectional"))
    )
    (net (code "37") (name "Net-(U$16-CO)") (class "Default")
      (node (ref "U$16") (pin "P$5") (pinfunction "CO_P$5") (pintype "bidirectional"))
      (node (ref "U$17") (pin "P$2") (pinfunction "CI_P$2") (pintype "bidirectional"))
    )
    (net (code "38") (name "Net-(U$16-DO)") (class "Default")
      (node (ref "U$16") (pin "P$6") (pinfunction "DO_P$6") (pintype "bidirectional"))
      (node (ref "U$17") (pin "P$1") (pinfunction "DI_P$1") (pintype "bidirectional"))
    )
    (net (code "39") (name "Net-(U$17-CO)") (class "Default")
      (node (ref "U$17") (pin "P$5") (pinfunction "CO_P$5") (pintype "bidirectional"))
      (node (ref "U$18") (pin "P$2") (pinfunction "CI_P$2") (pintype "bidirectional"))
    )
    (net (code "40") (name "Net-(U$17-DO)") (class "Default")
      (node (ref "U$17") (pin "P$6") (pinfunction "DO_P$6") (pintype "bidirectional"))
      (node (ref "U$18") (pin "P$1") (pinfunction "DI_P$1") (pintype "bidirectional"))
    )
    (net (code "41") (name "Net-(U$18-CO)") (class "Default")
      (node (ref "U$18") (pin "P$5") (pinfunction "CO_P$5") (pintype "bidirectional"))
      (node (ref "U$19") (pin "P$2") (pinfunction "CI_P$2") (pintype "bidirectional"))
    )
    (net (code "42") (name "Net-(U$18-DO)") (class "Default")
      (node (ref "U$18") (pin "P$6") (pinfunction "DO_P$6") (pintype "bidirectional"))
      (node (ref "U$19") (pin "P$1") (pinfunction "DI_P$1") (pintype "bidirectional"))
    )
    (net (code "43") (name "Net-(U$19-CO)") (class "Default")
      (node (ref "U$19") (pin "P$5") (pinfunction "CO_P$5") (pintype "bidirectional"))
      (node (ref "U$20") (pin "P$2") (pinfunction "CI_P$2") (pintype "bidirectional"))
    )
    (net (code "44") (name "Net-(U$19-DO)") (class "Default")
      (node (ref "U$19") (pin "P$6") (pinfunction "DO_P$6") (pintype "bidirectional"))
      (node (ref "U$20") (pin "P$1") (pinfunction "DI_P$1") (pintype "bidirectional"))
    )
    (net (code "45") (name "Net-(U$20-CO)") (class "Default")
      (node (ref "U$20") (pin "P$5") (pinfunction "CO_P$5") (pintype "bidirectional"))
      (node (ref "U$21") (pin "P$2") (pinfunction "CI_P$2") (pintype "bidirectional"))
    )
    (net (code "46") (name "Net-(U$20-DO)") (class "Default")
      (node (ref "U$20") (pin "P$6") (pinfunction "DO_P$6") (pintype "bidirectional"))
      (node (ref "U$21") (pin "P$1") (pinfunction "DI_P$1") (pintype "bidirectional"))
    )
    (net (code "47") (name "Net-(U$21-CO)") (class "Default")
      (node (ref "U$21") (pin "P$5") (pinfunction "CO_P$5") (pintype "bidirectional"))
      (node (ref "U$22") (pin "P$2") (pinfunction "CI_P$2") (pintype "bidirectional"))
    )
    (net (code "48") (name "Net-(U$21-DO)") (class "Default")
      (node (ref "U$21") (pin "P$6") (pinfunction "DO_P$6") (pintype "bidirectional"))
      (node (ref "U$22") (pin "P$1") (pinfunction "DI_P$1") (pintype "bidirectional"))
    )
    (net (code "49") (name "Net-(U$22-CO)") (class "Default")
      (node (ref "U$22") (pin "P$5") (pinfunction "CO_P$5") (pintype "bidirectional"))
      (node (ref "U$23") (pin "P$2") (pinfunction "CI_P$2") (pintype "bidirectional"))
    )
    (net (code "50") (name "Net-(U$22-DO)") (class "Default")
      (node (ref "U$22") (pin "P$6") (pinfunction "DO_P$6") (pintype "bidirectional"))
      (node (ref "U$23") (pin "P$1") (pinfunction "DI_P$1") (pintype "bidirectional"))
    )
    (net (code "51") (name "Net-(U$23-CO)") (class "Default")
      (node (ref "U$23") (pin "P$5") (pinfunction "CO_P$5") (pintype "bidirectional"))
      (node (ref "U$24") (pin "P$2") (pinfunction "CI_P$2") (pintype "bidirectional"))
    )
    (net (code "52") (name "Net-(U$23-DO)") (class "Default")
      (node (ref "U$23") (pin "P$6") (pinfunction "DO_P$6") (pintype "bidirectional"))
      (node (ref "U$24") (pin "P$1") (pinfunction "DI_P$1") (pintype "bidirectional"))
    )
    (net (code "53") (name "Net-(U$24-CO)") (class "Default")
      (node (ref "U$24") (pin "P$5") (pinfunction "CO_P$5") (pintype "bidirectional"))
      (node (ref "U$25") (pin "P$2") (pinfunction "CI_P$2") (pintype "bidirectional"))
    )
    (net (code "54") (name "Net-(U$24-DO)") (class "Default")
      (node (ref "U$24") (pin "P$6") (pinfunction "DO_P$6") (pintype "bidirectional"))
      (node (ref "U$25") (pin "P$1") (pinfunction "DI_P$1") (pintype "bidirectional"))
    )
    (net (code "55") (name "Net-(U$25-CO)") (class "Default")
      (node (ref "U$25") (pin "P$5") (pinfunction "CO_P$5") (pintype "bidirectional"))
      (node (ref "U$26") (pin "P$2") (pinfunction "CI_P$2") (pintype "bidirectional"))
    )
    (net (code "56") (name "Net-(U$25-DO)") (class "Default")
      (node (ref "U$25") (pin "P$6") (pinfunction "DO_P$6") (pintype "bidirectional"))
      (node (ref "U$26") (pin "P$1") (pinfunction "DI_P$1") (pintype "bidirectional"))
    )
    (net (code "57") (name "Net-(U$26-CO)") (class "Default")
      (node (ref "U$26") (pin "P$5") (pinfunction "CO_P$5") (pintype "bidirectional"))
      (node (ref "U$27") (pin "P$2") (pinfunction "CI_P$2") (pintype "bidirectional"))
    )
    (net (code "58") (name "Net-(U$26-DO)") (class "Default")
      (node (ref "U$26") (pin "P$6") (pinfunction "DO_P$6") (pintype "bidirectional"))
      (node (ref "U$27") (pin "P$1") (pinfunction "DI_P$1") (pintype "bidirectional"))
    )
    (net (code "59") (name "Net-(U$27-CO)") (class "Default")
      (node (ref "U$27") (pin "P$5") (pinfunction "CO_P$5") (pintype "bidirectional"))
      (node (ref "U$28") (pin "P$2") (pinfunction "CI_P$2") (pintype "bidirectional"))
    )
    (net (code "60") (name "Net-(U$27-DO)") (class "Default")
      (node (ref "U$27") (pin "P$6") (pinfunction "DO_P$6") (pintype "bidirectional"))
      (node (ref "U$28") (pin "P$1") (pinfunction "DI_P$1") (pintype "bidirectional"))
    )
    (net (code "61") (name "Net-(U$28-CO)") (class "Default")
      (node (ref "U$28") (pin "P$5") (pinfunction "CO_P$5") (pintype "bidirectional"))
      (node (ref "U$29") (pin "P$2") (pinfunction "CI_P$2") (pintype "bidirectional"))
    )
    (net (code "62") (name "Net-(U$28-DO)") (class "Default")
      (node (ref "U$28") (pin "P$6") (pinfunction "DO_P$6") (pintype "bidirectional"))
      (node (ref "U$29") (pin "P$1") (pinfunction "DI_P$1") (pintype "bidirectional"))
    )
    (net (code "63") (name "Net-(U$29-CO)") (class "Default")
      (node (ref "U$29") (pin "P$5") (pinfunction "CO_P$5") (pintype "bidirectional"))
      (node (ref "U$30") (pin "P$2") (pinfunction "CI_P$2") (pintype "bidirectional"))
    )
    (net (code "64") (name "Net-(U$29-DO)") (class "Default")
      (node (ref "U$29") (pin "P$6") (pinfunction "DO_P$6") (pintype "bidirectional"))
      (node (ref "U$30") (pin "P$1") (pinfunction "DI_P$1") (pintype "bidirectional"))
    )
    (net (code "65") (name "Net-(U$30-CO)") (class "Default")
      (node (ref "U$30") (pin "P$5") (pinfunction "CO_P$5") (pintype "bidirectional"))
      (node (ref "U$31") (pin "P$2") (pinfunction "CI_P$2") (pintype "bidirectional"))
    )
    (net (code "66") (name "Net-(U$30-DO)") (class "Default")
      (node (ref "U$30") (pin "P$6") (pinfunction "DO_P$6") (pintype "bidirectional"))
      (node (ref "U$31") (pin "P$1") (pinfunction "DI_P$1") (pintype "bidirectional"))
    )
    (net (code "67") (name "Net-(U$31-CO)") (class "Default")
      (node (ref "U$31") (pin "P$5") (pinfunction "CO_P$5") (pintype "bidirectional"))
      (node (ref "U$32") (pin "P$2") (pinfunction "CI_P$2") (pintype "bidirectional"))
    )
    (net (code "68") (name "Net-(U$31-DO)") (class "Default")
      (node (ref "U$31") (pin "P$6") (pinfunction "DO_P$6") (pintype "bidirectional"))
      (node (ref "U$32") (pin "P$1") (pinfunction "DI_P$1") (pintype "bidirectional"))
    )
    (net (code "69") (name "Net-(U$32-CO)") (class "Default")
      (node (ref "U$32") (pin "P$5") (pinfunction "CO_P$5") (pintype "bidirectional"))
      (node (ref "U$33") (pin "P$2") (pinfunction "CI_P$2") (pintype "bidirectional"))
    )
    (net (code "70") (name "Net-(U$32-DO)") (class "Default")
      (node (ref "U$32") (pin "P$6") (pinfunction "DO_P$6") (pintype "bidirectional"))
      (node (ref "U$33") (pin "P$1") (pinfunction "DI_P$1") (pintype "bidirectional"))
    )
    (net (code "71") (name "Net-(U$33-CO)") (class "Default")
      (node (ref "U$33") (pin "P$5") (pinfunction "CO_P$5") (pintype "bidirectional"))
      (node (ref "U$34") (pin "P$2") (pinfunction "CI_P$2") (pintype "bidirectional"))
    )
    (net (code "72") (name "Net-(U$33-DO)") (class "Default")
      (node (ref "U$33") (pin "P$6") (pinfunction "DO_P$6") (pintype "bidirectional"))
      (node (ref "U$34") (pin "P$1") (pinfunction "DI_P$1") (pintype "bidirectional"))
    )
    (net (code "73") (name "Net-(U$34-CO)") (class "Default")
      (node (ref "U$34") (pin "P$5") (pinfunction "CO_P$5") (pintype "bidirectional"))
      (node (ref "U$35") (pin "P$2") (pinfunction "CI_P$2") (pintype "bidirectional"))
    )
    (net (code "74") (name "Net-(U$34-DO)") (class "Default")
      (node (ref "U$34") (pin "P$6") (pinfunction "DO_P$6") (pintype "bidirectional"))
      (node (ref "U$35") (pin "P$1") (pinfunction "DI_P$1") (pintype "bidirectional"))
    )
    (net (code "75") (name "Net-(U$35-CO)") (class "Default")
      (node (ref "U$35") (pin "P$5") (pinfunction "CO_P$5") (pintype "bidirectional"))
      (node (ref "U$36") (pin "P$2") (pinfunction "CI_P$2") (pintype "bidirectional"))
    )
    (net (code "76") (name "Net-(U$35-DO)") (class "Default")
      (node (ref "U$35") (pin "P$6") (pinfunction "DO_P$6") (pintype "bidirectional"))
      (node (ref "U$36") (pin "P$1") (pinfunction "DI_P$1") (pintype "bidirectional"))
    )
    (net (code "77") (name "Net-(U$36-CO)") (class "Default")
      (node (ref "U$36") (pin "P$5") (pinfunction "CO_P$5") (pintype "bidirectional"))
      (node (ref "U$37") (pin "P$2") (pinfunction "CI_P$2") (pintype "bidirectional"))
    )
    (net (code "78") (name "Net-(U$36-DO)") (class "Default")
      (node (ref "U$36") (pin "P$6") (pinfunction "DO_P$6") (pintype "bidirectional"))
      (node (ref "U$37") (pin "P$1") (pinfunction "DI_P$1") (pintype "bidirectional"))
    )
    (net (code "79") (name "Net-(U$37-CO)") (class "Default")
      (node (ref "U$37") (pin "P$5") (pinfunction "CO_P$5") (pintype "bidirectional"))
      (node (ref "U$38") (pin "P$2") (pinfunction "CI_P$2") (pintype "bidirectional"))
    )
    (net (code "80") (name "Net-(U$37-DO)") (class "Default")
      (node (ref "U$37") (pin "P$6") (pinfunction "DO_P$6") (pintype "bidirectional"))
      (node (ref "U$38") (pin "P$1") (pinfunction "DI_P$1") (pintype "bidirectional"))
    )
    (net (code "81") (name "Net-(U$38-CO)") (class "Default")
      (node (ref "U$38") (pin "P$5") (pinfunction "CO_P$5") (pintype "bidirectional"))
      (node (ref "U$39") (pin "P$2") (pinfunction "CI_P$2") (pintype "bidirectional"))
    )
    (net (code "82") (name "Net-(U$38-DO)") (class "Default")
      (node (ref "U$38") (pin "P$6") (pinfunction "DO_P$6") (pintype "bidirectional"))
      (node (ref "U$39") (pin "P$1") (pinfunction "DI_P$1") (pintype "bidirectional"))
    )
    (net (code "83") (name "Net-(U$39-CO)") (class "Default")
      (node (ref "U$39") (pin "P$5") (pinfunction "CO_P$5") (pintype "bidirectional"))
      (node (ref "U$40") (pin "P$2") (pinfunction "CI_P$2") (pintype "bidirectional"))
    )
    (net (code "84") (name "Net-(U$39-DO)") (class "Default")
      (node (ref "U$39") (pin "P$6") (pinfunction "DO_P$6") (pintype "bidirectional"))
      (node (ref "U$40") (pin "P$1") (pinfunction "DI_P$1") (pintype "bidirectional"))
    )
    (net (code "85") (name "unconnected-(AD-Pad1)") (class "Default")
      (node (ref "AD") (pin "1") (pinfunction "1_1") (pintype "passive"))
    )
    (net (code "86") (name "unconnected-(AD-Pad2)") (class "Default")
      (node (ref "AD") (pin "2") (pinfunction "2_2") (pintype "passive"))
    )
    (net (code "87") (name "unconnected-(AD-Pad3)") (class "Default")
      (node (ref "AD") (pin "3") (pinfunction "3_3") (pintype "passive"))
    )
    (net (code "88") (name "unconnected-(AD-Pad4)") (class "Default")
      (node (ref "AD") (pin "4") (pinfunction "4_4") (pintype "passive"))
    )
    (net (code "89") (name "unconnected-(AD-Pad5)") (class "Default")
      (node (ref "AD") (pin "5") (pinfunction "5_5") (pintype "passive"))
    )
    (net (code "90") (name "unconnected-(AD-Pad6)") (class "Default")
      (node (ref "AD") (pin "6") (pinfunction "6_6") (pintype "passive"))
    )
    (net (code "91") (name "unconnected-(IOH-Pad1)") (class "Default")
      (node (ref "IOH") (pin "1") (pinfunction "1_1") (pintype "passive"))
    )
    (net (code "92") (name "unconnected-(IOH-Pad2)") (class "Default")
      (node (ref "IOH") (pin "2") (pinfunction "2_2") (pintype "passive"))
    )
    (net (code "93") (name "unconnected-(IOH-Pad3)") (class "Default")
      (node (ref "IOH") (pin "3") (pinfunction "3_3") (pintype "passive"))
    )
    (net (code "94") (name "unconnected-(IOH-Pad5)") (class "Default")
      (node (ref "IOH") (pin "5") (pinfunction "5_5") (pintype "passive"))
    )
    (net (code "95") (name "unconnected-(IOH-Pad8)") (class "Default")
      (node (ref "IOH") (pin "8") (pinfunction "8_8") (pintype "passive"))
    )
    (net (code "96") (name "unconnected-(IOH-Pad9)") (class "Default")
      (node (ref "IOH") (pin "9") (pinfunction "9_9") (pintype "passive"))
    )
    (net (code "97") (name "unconnected-(IOH-Pad10)") (class "Default")
      (node (ref "IOH") (pin "10") (pinfunction "10_10") (pintype "passive"))
    )
    (net (code "98") (name "unconnected-(IOL-Pad1)") (class "Default")
      (node (ref "IOL") (pin "1") (pinfunction "1_1") (pintype "passive"))
    )
    (net (code "99") (name "unconnected-(IOL-Pad2)") (class "Default")
      (node (ref "IOL") (pin "2") (pinfunction "2_2") (pintype "passive"))
    )
    (net (code "100") (name "unconnected-(IOL-Pad3)") (class "Default")
      (node (ref "IOL") (pin "3") (pinfunction "3_3") (pintype "passive"))
    )
    (net (code "101") (name "unconnected-(IOL-Pad4)") (class "Default")
      (node (ref "IOL") (pin "4") (pinfunction "4_4") (pintype "passive"))
    )
    (net (code "102") (name "unconnected-(IOL-Pad5)") (class "Default")
      (node (ref "IOL") (pin "5") (pinfunction "5_5") (pintype "passive"))
    )
    (net (code "103") (name "unconnected-(IOL-Pad6)") (class "Default")
      (node (ref "IOL") (pin "6") (pinfunction "6_6") (pintype "passive"))
    )
    (net (code "104") (name "unconnected-(IOL-Pad7)") (class "Default")
      (node (ref "IOL") (pin "7") (pinfunction "7_7") (pintype "passive"))
    )
    (net (code "105") (name "unconnected-(IOL-Pad8)") (class "Default")
      (node (ref "IOL") (pin "8") (pinfunction "8_8") (pintype "passive"))
    )
    (net (code "106") (name "unconnected-(POWER-Pad1)") (class "Default")
      (node (ref "POWER") (pin "1") (pinfunction "1_1") (pintype "passive"))
    )
    (net (code "107") (name "unconnected-(POWER-Pad2)") (class "Default")
      (node (ref "POWER") (pin "2") (pinfunction "2_2") (pintype "passive"))
    )
    (net (code "108") (name "unconnected-(POWER-Pad3)") (class "Default")
      (node (ref "POWER") (pin "3") (pinfunction "3_3") (pintype "passive"))
    )
    (net (code "109") (name "unconnected-(POWER-Pad4)") (class "Default")
      (node (ref "POWER") (pin "4") (pinfunction "4_4") (pintype "passive"))
    )
    (net (code "110") (name "unconnected-(POWER-Pad8)") (class "Default")
      (node (ref "POWER") (pin "8") (pinfunction "8_8") (pintype "passive"))
    )
    (net (code "111") (name "unconnected-(U$40-CO-PadP$5)") (class "Default")
      (node (ref "U$40") (pin "P$5") (pinfunction "CO_P$5") (pintype "bidirectional"))
    )
    (net (code "112") (name "unconnected-(U$40-DO-PadP$6)") (class "Default")
      (node (ref "U$40") (pin "P$6") (pinfunction "DO_P$6") (pintype "bidirectional"))
    )
  )
)
